# k1fm-pico-power.net
KiCad netlist of a schematic drawn in EAGLE
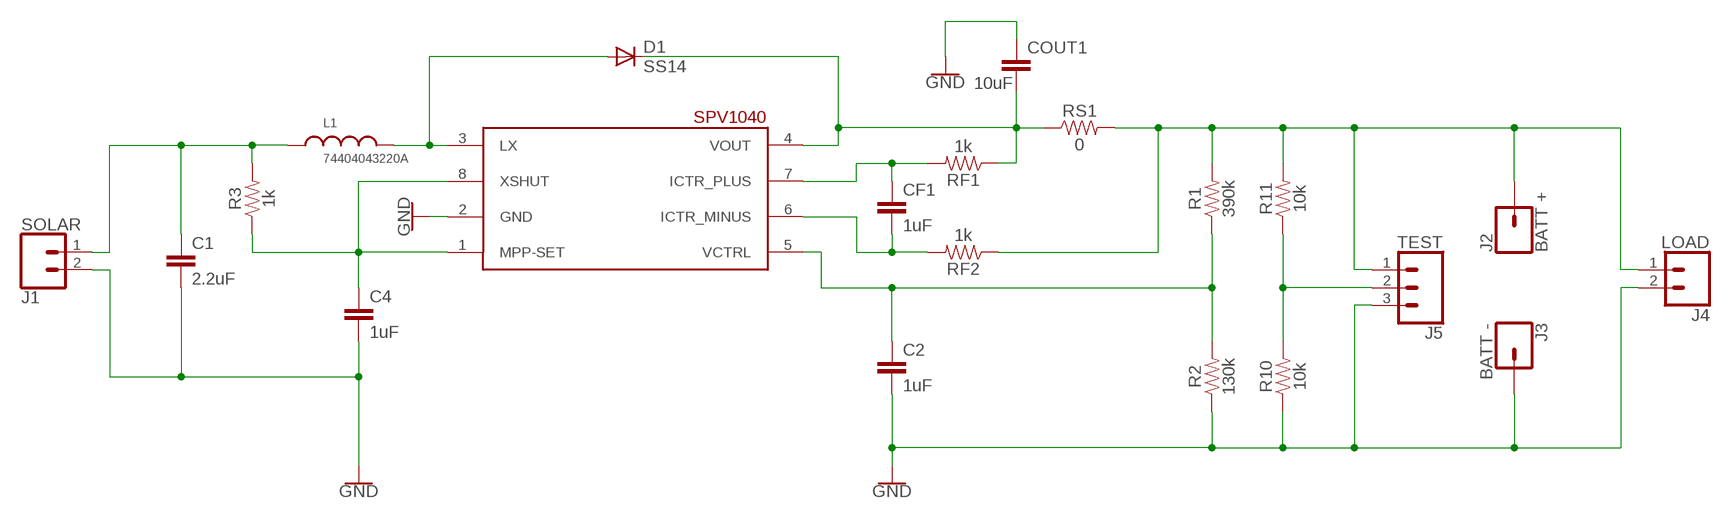
[diagram p0: schematic, sheet 1]

(export (version "E")
  (design (tool "Eeschema 10.0.6"))
  (components
    (comp (ref "C1")
      (value "2.2uF")
      (footprint "eagle-import:0603")
      (libsource (lib "eagle-import") (part "3.0NF-0603-50V-5%"))
    )
    (comp (ref "C2")
      (value "1uF")
      (footprint "eagle-import:0603")
      (libsource (lib "eagle-import") (part "3.0NF-0603-50V-5%"))
    )
    (comp (ref "C4")
      (value "1uF")
      (footprint "eagle-import:0603")
      (libsource (lib "eagle-import") (part "3.0NF-0603-50V-5%"))
    )
    (comp (ref "CF1")
      (value "1uF")
      (footprint "eagle-import:0603")
      (libsource (lib "eagle-import") (part "3.0NF-0603-50V-5%"))
    )
    (comp (ref "COUT1")
      (value "10uF")
      (footprint "eagle-import:0603")
      (libsource (lib "eagle-import") (part "3.0NF-0603-50V-5%"))
    )
    (comp (ref "D1")
      (value "SS14")
      (footprint "eagle-import:DO-214AC")
      (libsource (lib "eagle-import") (part "DIODE-DO-214AC"))
    )
    (comp (ref "J1")
      (value "SOLAR")
      (footprint "eagle-import:1X02")
      (libsource (lib "eagle-import") (part "CONN_02"))
    )
    (comp (ref "J2")
      (value "BATT +")
      (footprint "eagle-import:1X01")
      (libsource (lib "eagle-import") (part "CONN_01"))
    )
    (comp (ref "J3")
      (value "BATT -")
      (footprint "eagle-import:1X01")
      (libsource (lib "eagle-import") (part "CONN_01"))
    )
    (comp (ref "J4")
      (value "LOAD")
      (footprint "eagle-import:1X02")
      (libsource (lib "eagle-import") (part "CONN_02"))
    )
    (comp (ref "J5")
      (value "TEST")
      (footprint "eagle-import:1X03")
      (libsource (lib "eagle-import") (part "CONN_03"))
    )
    (comp (ref "L1")
      (value "74404043220A")
      (footprint "eagle-import:WE-LQS_4025")
      (libsource (lib "eagle-import") (part "WE-LQS_4025_74404043220A"))
    )
    (comp (ref "R1")
      (value "390k")
      (footprint "eagle-import:0603")
      (libsource (lib "eagle-import") (part "390KOHM-0603-1/10W-1%"))
    )
    (comp (ref "R2")
      (value "130k")
      (footprint "eagle-import:0603")
      (libsource (lib "eagle-import") (part "150KOHM-0603-1/10W-1%"))
    )
    (comp (ref "R3")
      (value "1k")
      (footprint "eagle-import:0603")
      (libsource (lib "eagle-import") (part "1KOHM-0603-1/10W-1%"))
    )
    (comp (ref "R10")
      (value "10k")
      (footprint "eagle-import:0603")
      (libsource (lib "eagle-import") (part "150KOHM-0603-1/10W-1%"))
    )
    (comp (ref "R11")
      (value "10k")
      (footprint "eagle-import:0603")
      (libsource (lib "eagle-import") (part "150KOHM-0603-1/10W-1%"))
    )
    (comp (ref "RF1")
      (value "1k")
      (footprint "eagle-import:0603")
      (libsource (lib "eagle-import") (part "1KOHM-0603-1/10W-1%"))
    )
    (comp (ref "RF2")
      (value "1k")
      (footprint "eagle-import:0603")
      (libsource (lib "eagle-import") (part "1KOHM-0603-1/10W-1%"))
    )
    (comp (ref "RS1")
      (value "0")
      (footprint "eagle-import:0603")
      (libsource (lib "eagle-import") (part "1KOHM-0603-1/10W-1%"))
    )
    (comp (ref "U1")
      (value "SPV1040")
      (footprint "eagle-import:TSSOP-8")
      (libsource (lib "eagle-import") (part "SPV1040"))
    )
  )
  (nets
    (net (code "1") (name "GND") (class "Default")
      (node (ref "C1") (pin "2") (pinfunction "2_2") (pintype "passive"))
      (node (ref "C2") (pin "2") (pinfunction "2_2") (pintype "passive"))
      (node (ref "C4") (pin "2") (pinfunction "2_2") (pintype "passive"))
      (node (ref "COUT1") (pin "1") (pinfunction "1_1") (pintype "passive"))
      (node (ref "J1") (pin "2") (pinfunction "2_2") (pintype "passive"))
      (node (ref "J3") (pin "1") (pinfunction "1_1") (pintype "passive"))
      (node (ref "J4") (pin "2") (pinfunction "2_2") (pintype "passive"))
      (node (ref "J5") (pin "3") (pinfunction "3_3") (pintype "passive"))
      (node (ref "R10") (pin "1") (pinfunction "1_1") (pintype "passive"))
      (node (ref "R2") (pin "1") (pinfunction "1_1") (pintype "passive"))
      (node (ref "U1") (pin "2") (pinfunction "GND_2") (pintype "bidirectional"))
    )
    (net (code "2") (name "Net-(C1-Pad1)") (class "Default")
      (node (ref "C1") (pin "1") (pinfunction "1_1") (pintype "passive"))
      (node (ref "J1") (pin "1") (pinfunction "1_1") (pintype "passive"))
      (node (ref "L1") (pin "1") (pinfunction "1_1") (pintype "passive"))
      (node (ref "R3") (pin "2") (pinfunction "2_2") (pintype "passive"))
    )
    (net (code "3") (name "Net-(J2-Pad1)") (class "Default")
      (node (ref "J2") (pin "1") (pinfunction "1_1") (pintype "passive"))
      (node (ref "J4") (pin "1") (pinfunction "1_1") (pintype "passive"))
      (node (ref "J5") (pin "1") (pinfunction "1_1") (pintype "passive"))
      (node (ref "R1") (pin "2") (pinfunction "2_2") (pintype "passive"))
      (node (ref "R11") (pin "2") (pinfunction "2_2") (pintype "passive"))
      (node (ref "RF2") (pin "1") (pinfunction "1_1") (pintype "passive"))
      (node (ref "RS1") (pin "2") (pinfunction "2_2") (pintype "passive"))
    )
    (net (code "4") (name "Net-(J5-Pad2)") (class "Default")
      (node (ref "J5") (pin "2") (pinfunction "2_2") (pintype "passive"))
      (node (ref "R10") (pin "2") (pinfunction "2_2") (pintype "passive"))
      (node (ref "R11") (pin "1") (pinfunction "1_1") (pintype "passive"))
    )
    (net (code "5") (name "Net-(U1-ICTR_MINUS)") (class "Default")
      (node (ref "CF1") (pin "2") (pinfunction "2_2") (pintype "passive"))
      (node (ref "RF2") (pin "2") (pinfunction "2_2") (pintype "passive"))
      (node (ref "U1") (pin "6") (pinfunction "ICTR_MINUS_6") (pintype "bidirectional"))
    )
    (net (code "6") (name "Net-(U1-ICTR_PLUS)") (class "Default")
      (node (ref "CF1") (pin "1") (pinfunction "1_1") (pintype "passive"))
      (node (ref "RF1") (pin "2") (pinfunction "2_2") (pintype "passive"))
      (node (ref "U1") (pin "7") (pinfunction "ICTR_PLUS_7") (pintype "bidirectional"))
    )
    (net (code "7") (name "Net-(U1-LX)") (class "Default")
      (node (ref "D1") (pin "A") (pinfunction "A_A") (pintype "passive"))
      (node (ref "L1") (pin "2") (pinfunction "2_2") (pintype "passive"))
      (node (ref "U1") (pin "3") (pinfunction "LX_3") (pintype "bidirectional"))
    )
    (net (code "8") (name "Net-(U1-MPP-SET)") (class "Default")
      (node (ref "C4") (pin "1") (pinfunction "1_1") (pintype "passive"))
      (node (ref "R3") (pin "1") (pinfunction "1_1") (pintype "passive"))
      (node (ref "U1") (pin "1") (pinfunction "MPP-SET_1") (pintype "bidirectional"))
      (node (ref "U1") (pin "8") (pinfunction "XSHUT_8") (pintype "bidirectional"))
    )
    (net (code "9") (name "Net-(U1-VCTRL)") (class "Default")
      (node (ref "C2") (pin "1") (pinfunction "1_1") (pintype "passive"))
      (node (ref "R1") (pin "1") (pinfunction "1_1") (pintype "passive"))
      (node (ref "R2") (pin "2") (pinfunction "2_2") (pintype "passive"))
      (node (ref "U1") (pin "5") (pinfunction "VCTRL_5") (pintype "bidirectional"))
    )
    (net (code "10") (name "Net-(U1-VOUT)") (class "Default")
      (node (ref "COUT1") (pin "2") (pinfunction "2_2") (pintype "passive"))
      (node (ref "D1") (pin "C") (pinfunction "C_C") (pintype "passive"))
      (node (ref "RF1") (pin "1") (pinfunction "1_1") (pintype "passive"))
      (node (ref "RS1") (pin "1") (pinfunction "1_1") (pintype "passive"))
      (node (ref "U1") (pin "4") (pinfunction "VOUT_4") (pintype "bidirectional"))
    )
  )
)
